# MainBoard_V1.net
KiCad netlist of a schematic drawn in EAGLE
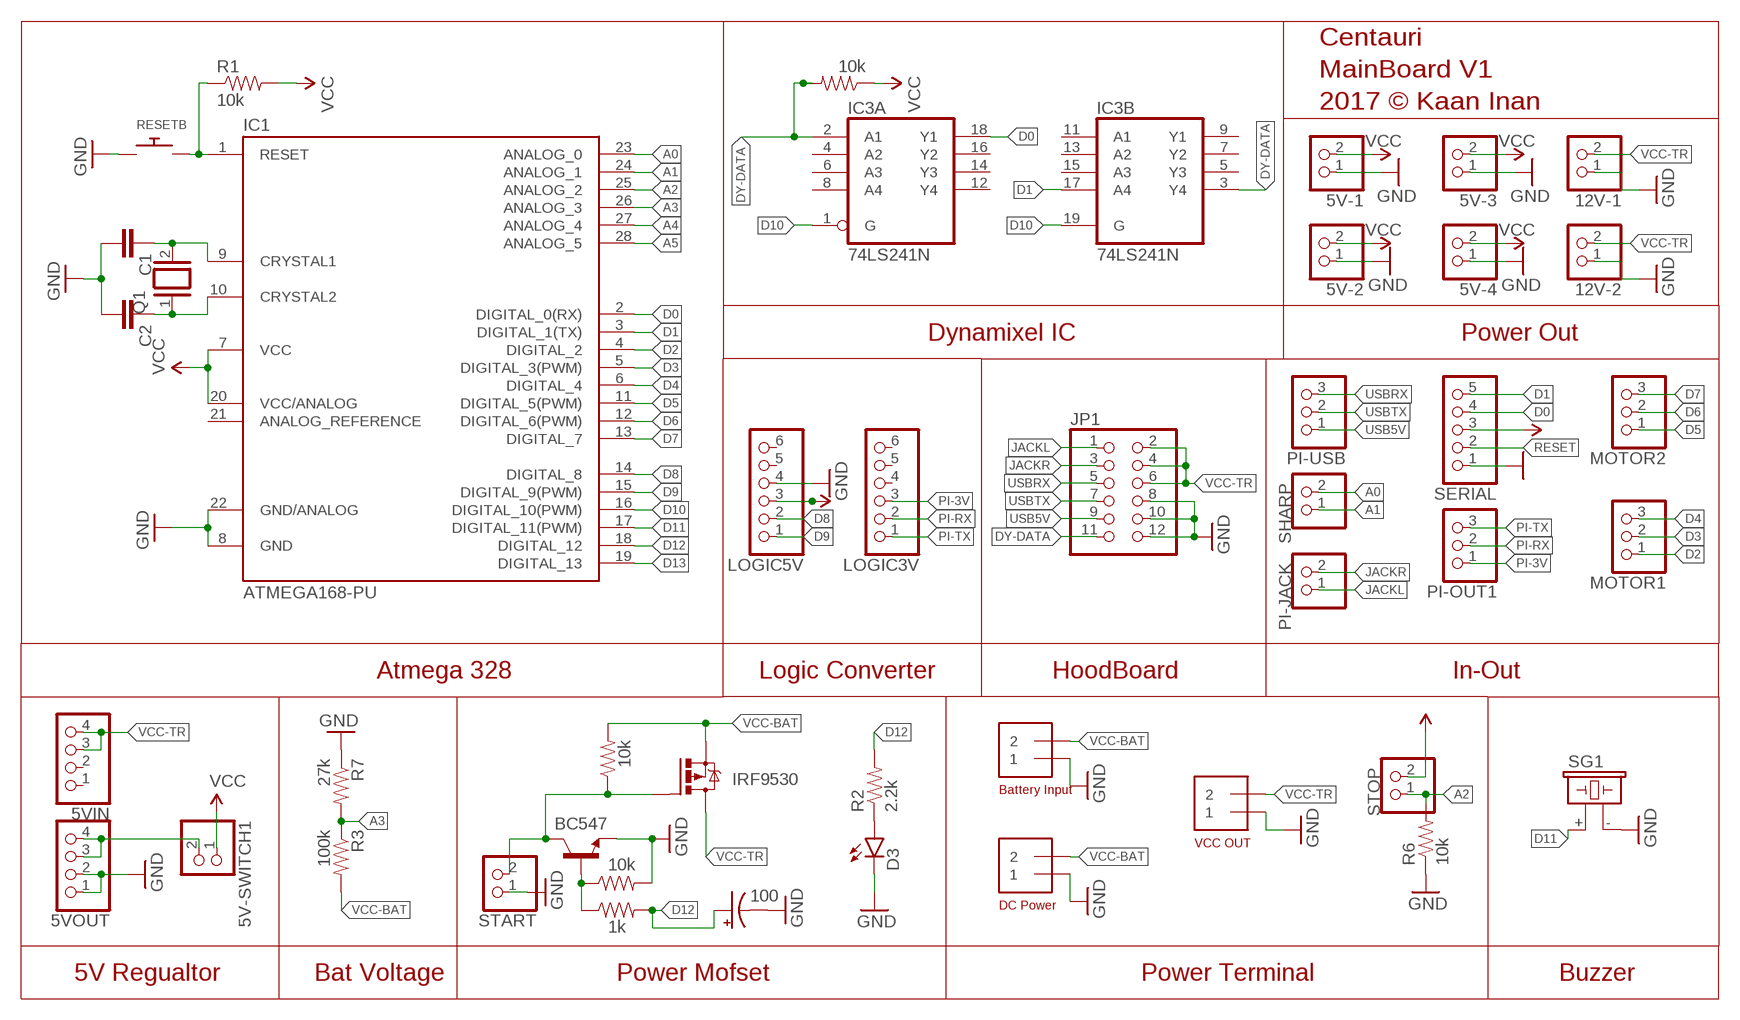
[diagram p0: schematic, sheet 1]

(export (version "E")
  (design (tool "Eeschema 10.0.6"))
  (components
    (comp (ref "5V-1")
      (value "PINHD-1X2/90")
      (footprint "eagle-import:1X02_90")
      (libsource (lib "eagle-import") (part "PINHD-1X2/90"))
    )
    (comp (ref "5V-2")
      (value "PINHD-1X2/90")
      (footprint "eagle-import:1X02_90")
      (libsource (lib "eagle-import") (part "PINHD-1X2/90"))
    )
    (comp (ref "5V-3")
      (value "PINHD-1X2/90")
      (footprint "eagle-import:1X02_90")
      (libsource (lib "eagle-import") (part "PINHD-1X2/90"))
    )
    (comp (ref "5V-4")
      (value "PINHD-1X2/90")
      (footprint "eagle-import:1X02_90")
      (libsource (lib "eagle-import") (part "PINHD-1X2/90"))
    )
    (comp (ref "5V-SWITCH1")
      (value "PINHD-1X2")
      (footprint "eagle-import:1X02")
      (libsource (lib "eagle-import") (part "PINHD-1X2"))
    )
    (comp (ref "5VIN")
      (value "PINHD-1X4")
      (footprint "eagle-import:1X04")
      (libsource (lib "eagle-import") (part "PINHD-1X4"))
    )
    (comp (ref "5VOUT")
      (value "PINHD-1X4")
      (footprint "eagle-import:1X04")
      (libsource (lib "eagle-import") (part "PINHD-1X4"))
    )
    (comp (ref "12V-1")
      (value "PINHD-1X2/90")
      (footprint "eagle-import:1X02_90")
      (libsource (lib "eagle-import") (part "PINHD-1X2/90"))
    )
    (comp (ref "12V-2")
      (value "PINHD-1X2/90")
      (footprint "eagle-import:1X02_90")
      (libsource (lib "eagle-import") (part "PINHD-1X2/90"))
    )
    (comp (ref "C1")
      (value "0.1UF-50V-20%(PTH)KIT-EZ")
      (footprint "eagle-import:CAP-PTH-SMALL-KIT")
      (libsource (lib "eagle-import") (part "0.1UF-50V-20%(PTH)KIT-EZ"))
    )
    (comp (ref "C2")
      (value "0.1UF-50V-20%(PTH)KIT-EZ")
      (footprint "eagle-import:CAP-PTH-SMALL-KIT")
      (libsource (lib "eagle-import") (part "0.1UF-50V-20%(PTH)KIT-EZ"))
    )
    (comp (ref "C7")
      (value "100")
      (footprint "eagle-import:CPOL-RADIAL-100UF-25V")
      (libsource (lib "eagle-import") (part "100UF-25V-20%(PTH)"))
    )
    (comp (ref "D3")
      (value "LED3MM")
      (footprint "eagle-import:LED3MM")
      (libsource (lib "eagle-import") (part "LED3MM"))
    )
    (comp (ref "DC1")
      (value "1X2-3.5MM")
      (footprint "eagle-import:1X2-3.5MM")
      (libsource (lib "eagle-import") (part "1X2-3.5MM"))
    )
    (comp (ref "IC1")
      (value "ATMEGA168-PU")
      (footprint "eagle-import:DIL28-3")
      (libsource (lib "eagle-import") (part "ATMEGA168-PU"))
    )
    (comp (ref "IC3")
      (value "74LS241N")
      (footprint "eagle-import:DIL20")
      (libsource (lib "eagle-import") (part "74241NLS"))
    )
    (comp (ref "JP1")
      (value "PINHD-2X6")
      (footprint "eagle-import:2X06")
      (libsource (lib "eagle-import") (part "PINHD-2X6"))
    )
    (comp (ref "LOGIC3V")
      (value "PINHD-1X6")
      (footprint "eagle-import:1X06")
      (libsource (lib "eagle-import") (part "PINHD-1X6"))
    )
    (comp (ref "LOGIC5V")
      (value "PINHD-1X6")
      (footprint "eagle-import:1X06")
      (libsource (lib "eagle-import") (part "PINHD-1X6"))
    )
    (comp (ref "MOTOR1")
      (value "PINHD-1X3")
      (footprint "eagle-import:1X03")
      (libsource (lib "eagle-import") (part "PINHD-1X3"))
    )
    (comp (ref "MOTOR2")
      (value "PINHD-1X3")
      (footprint "eagle-import:1X03")
      (libsource (lib "eagle-import") (part "PINHD-1X3"))
    )
    (comp (ref "PI-JACK")
      (value "PINHD-1X2")
      (footprint "eagle-import:1X02")
      (libsource (lib "eagle-import") (part "PINHD-1X2"))
    )
    (comp (ref "PI-OUT1")
      (value "PINHD-1X3")
      (footprint "eagle-import:1X03")
      (libsource (lib "eagle-import") (part "PINHD-1X3"))
    )
    (comp (ref "PI-USB")
      (value "PINHD-1X3")
      (footprint "eagle-import:1X03")
      (libsource (lib "eagle-import") (part "PINHD-1X3"))
    )
    (comp (ref "PIL1")
      (value "1X2-3.5MM")
      (footprint "eagle-import:1X2-3.5MM")
      (libsource (lib "eagle-import") (part "1X2-3.5MM"))
    )
    (comp (ref "Q1")
      (value "XTAL/S")
      (footprint "eagle-import:QS")
      (libsource (lib "eagle-import") (part "XTAL/S"))
    )
    (comp (ref "Q2")
      (value "IRF9530")
      (footprint "eagle-import:TO220BV")
      (libsource (lib "eagle-import") (part "IRF9530"))
    )
    (comp (ref "Q6")
      (value "BC547")
      (footprint "eagle-import:TO-92")
      (libsource (lib "eagle-import") (part "TRANSISTOR_NPN2N3904"))
    )
    (comp (ref "R1")
      (value "10k")
      (footprint "eagle-import:AXIAL-0.3")
      (libsource (lib "eagle-import") (part "RESISTORAXIAL-0.3"))
    )
    (comp (ref "R2")
      (value "2.2k")
      (footprint "eagle-import:AXIAL-0.3")
      (libsource (lib "eagle-import") (part "RESISTORAXIAL-0.3"))
    )
    (comp (ref "R3")
      (value "100k")
      (footprint "eagle-import:AXIAL-0.3")
      (libsource (lib "eagle-import") (part "RESISTORAXIAL-0.3"))
    )
    (comp (ref "R6")
      (value "10k")
      (footprint "eagle-import:AXIAL-0.3")
      (libsource (lib "eagle-import") (part "RESISTORAXIAL-0.3"))
    )
    (comp (ref "R7")
      (value "27k")
      (footprint "eagle-import:AXIAL-0.3")
      (libsource (lib "eagle-import") (part "RESISTORAXIAL-0.3"))
    )
    (comp (ref "R8")
      (value "10k")
      (footprint "eagle-import:AXIAL-0.3")
      (libsource (lib "eagle-import") (part "RESISTORAXIAL-0.3"))
    )
    (comp (ref "R17")
      (value "10k")
      (footprint "eagle-import:AXIAL-0.3")
      (libsource (lib "eagle-import") (part "RESISTORAXIAL-0.3"))
    )
    (comp (ref "R19")
      (value "10k")
      (footprint "eagle-import:AXIAL-0.3")
      (libsource (lib "eagle-import") (part "RESISTORAXIAL-0.3"))
    )
    (comp (ref "R20")
      (value "1k")
      (footprint "eagle-import:AXIAL-0.3")
      (libsource (lib "eagle-import") (part "RESISTORAXIAL-0.3"))
    )
    (comp (ref "RESETB")
      (value "SWITCH_PUSHBUTTONEVQ-PE")
      (footprint "eagle-import:TACT_PANA-EVQ")
      (libsource (lib "eagle-import") (part "SWITCH_PUSHBUTTONEVQ-PE"))
    )
    (comp (ref "SERIAL")
      (value "PINHD-1X5")
      (footprint "eagle-import:1X05")
      (libsource (lib "eagle-import") (part "PINHD-1X5"))
    )
    (comp (ref "SG1")
      (value "F/CM12P")
      (footprint "eagle-import:F_CM12P")
      (libsource (lib "eagle-import") (part "F/CM12P"))
    )
    (comp (ref "SHARP")
      (value "PINHD-1X2")
      (footprint "eagle-import:1X02")
      (libsource (lib "eagle-import") (part "PINHD-1X2"))
    )
    (comp (ref "START")
      (value "PINHD-1X2")
      (footprint "eagle-import:1X02")
      (libsource (lib "eagle-import") (part "PINHD-1X2"))
    )
    (comp (ref "STOP")
      (value "PINHD-1X2")
      (footprint "eagle-import:1X02")
      (libsource (lib "eagle-import") (part "PINHD-1X2"))
    )
    (comp (ref "VCC1")
      (value "1X2-3.5MM")
      (footprint "eagle-import:1X2-3.5MM")
      (libsource (lib "eagle-import") (part "1X2-3.5MM"))
    )
  )
  (nets
    (net (code "1") (name "A0") (class "Default")
      (node (ref "IC1") (pin "23") (pinfunction "ANALOG_0_23") (pintype "bidirectional"))
      (node (ref "SHARP") (pin "2") (pinfunction "2_2") (pintype "passive"))
    )
    (net (code "2") (name "A1") (class "Default")
      (node (ref "IC1") (pin "24") (pinfunction "ANALOG_1_24") (pintype "bidirectional"))
      (node (ref "SHARP") (pin "1") (pinfunction "1_1") (pintype "passive"))
    )
    (net (code "3") (name "A2") (class "Default")
      (node (ref "IC1") (pin "25") (pinfunction "ANALOG_2_25") (pintype "bidirectional"))
      (node (ref "R6") (pin "P$2") (pinfunction "2_P$2") (pintype "passive"))
      (node (ref "STOP") (pin "1") (pinfunction "1_1") (pintype "passive"))
    )
    (net (code "4") (name "A3") (class "Default")
      (node (ref "IC1") (pin "26") (pinfunction "ANALOG_3_26") (pintype "bidirectional"))
      (node (ref "R3") (pin "P$1") (pinfunction "1_P$1") (pintype "passive"))
      (node (ref "R7") (pin "P$2") (pinfunction "2_P$2") (pintype "passive"))
    )
    (net (code "5") (name "A4") (class "Default")
      (node (ref "IC1") (pin "27") (pinfunction "ANALOG_4_27") (pintype "bidirectional"))
    )
    (net (code "6") (name "A5") (class "Default")
      (node (ref "IC1") (pin "28") (pinfunction "ANALOG_5_28") (pintype "bidirectional"))
    )
    (net (code "7") (name "D0") (class "Default")
      (node (ref "IC1") (pin "2") (pinfunction "DIGITAL_0(RX)_2") (pintype "bidirectional"))
      (node (ref "IC3") (pin "18") (pinfunction "Y1_18") (pintype "tri_state"))
      (node (ref "SERIAL") (pin "4") (pinfunction "4_4") (pintype "passive"))
    )
    (net (code "8") (name "D1") (class "Default")
      (node (ref "IC1") (pin "3") (pinfunction "DIGITAL_1(TX)_3") (pintype "bidirectional"))
      (node (ref "IC3") (pin "17") (pinfunction "A4_17") (pintype "input"))
      (node (ref "SERIAL") (pin "5") (pinfunction "5_5") (pintype "passive"))
    )
    (net (code "9") (name "D2") (class "Default")
      (node (ref "IC1") (pin "4") (pinfunction "DIGITAL_2_4") (pintype "bidirectional"))
      (node (ref "MOTOR1") (pin "1") (pinfunction "1_1") (pintype "passive"))
    )
    (net (code "10") (name "D3") (class "Default")
      (node (ref "IC1") (pin "5") (pinfunction "DIGITAL_3(PWM)_5") (pintype "bidirectional"))
      (node (ref "MOTOR1") (pin "2") (pinfunction "2_2") (pintype "passive"))
    )
    (net (code "11") (name "D4") (class "Default")
      (node (ref "IC1") (pin "6") (pinfunction "DIGITAL_4_6") (pintype "bidirectional"))
      (node (ref "MOTOR1") (pin "3") (pinfunction "3_3") (pintype "passive"))
    )
    (net (code "12") (name "D5") (class "Default")
      (node (ref "IC1") (pin "11") (pinfunction "DIGITAL_5(PWM)_11") (pintype "bidirectional"))
      (node (ref "MOTOR2") (pin "1") (pinfunction "1_1") (pintype "passive"))
    )
    (net (code "13") (name "D6") (class "Default")
      (node (ref "IC1") (pin "12") (pinfunction "DIGITAL_6(PWM)_12") (pintype "bidirectional"))
      (node (ref "MOTOR2") (pin "2") (pinfunction "2_2") (pintype "passive"))
    )
    (net (code "14") (name "D7") (class "Default")
      (node (ref "IC1") (pin "13") (pinfunction "DIGITAL_7_13") (pintype "bidirectional"))
      (node (ref "MOTOR2") (pin "3") (pinfunction "3_3") (pintype "passive"))
    )
    (net (code "15") (name "D8") (class "Default")
      (node (ref "IC1") (pin "14") (pinfunction "DIGITAL_8_14") (pintype "bidirectional"))
      (node (ref "LOGIC5V") (pin "2") (pinfunction "2_2") (pintype "passive"))
    )
    (net (code "16") (name "D9") (class "Default")
      (node (ref "IC1") (pin "15") (pinfunction "DIGITAL_9(PWM)_15") (pintype "bidirectional"))
      (node (ref "LOGIC5V") (pin "1") (pinfunction "1_1") (pintype "passive"))
    )
    (net (code "17") (name "D10") (class "Default")
      (node (ref "IC1") (pin "16") (pinfunction "DIGITAL_10(PWM)_16") (pintype "bidirectional"))
      (node (ref "IC3") (pin "1") (pinfunction "G_1") (pintype "input"))
      (node (ref "IC3") (pin "19") (pinfunction "G_19") (pintype "input"))
    )
    (net (code "18") (name "D11") (class "Default")
      (node (ref "IC1") (pin "17") (pinfunction "DIGITAL_11(PWM)_17") (pintype "bidirectional"))
      (node (ref "SG1") (pin "+") (pinfunction "1_+") (pintype "passive"))
    )
    (net (code "19") (name "D12") (class "Default")
      (node (ref "C7") (pin "1") (pinfunction "+_1") (pintype "passive"))
      (node (ref "IC1") (pin "18") (pinfunction "DIGITAL_12_18") (pintype "bidirectional"))
      (node (ref "R2") (pin "P$2") (pinfunction "2_P$2") (pintype "passive"))
      (node (ref "R20") (pin "P$2") (pinfunction "2_P$2") (pintype "passive"))
    )
    (net (code "20") (name "D13") (class "Default")
      (node (ref "IC1") (pin "19") (pinfunction "DIGITAL_13_19") (pintype "bidirectional"))
    )
    (net (code "21") (name "DY-DATA") (class "Default")
      (node (ref "IC3") (pin "2") (pinfunction "A1_2") (pintype "input"))
      (node (ref "IC3") (pin "3") (pinfunction "Y4_3") (pintype "tri_state"))
      (node (ref "JP1") (pin "11") (pinfunction "11_11") (pintype "passive"))
      (node (ref "R8") (pin "P$2") (pinfunction "2_P$2") (pintype "passive"))
    )
    (net (code "22") (name "GND") (class "Default")
      (node (ref "12V-1") (pin "1") (pinfunction "1_1") (pintype "passive"))
      (node (ref "12V-2") (pin "1") (pinfunction "1_1") (pintype "passive"))
      (node (ref "5V-1") (pin "1") (pinfunction "1_1") (pintype "passive"))
      (node (ref "5V-2") (pin "1") (pinfunction "1_1") (pintype "passive"))
      (node (ref "5V-3") (pin "1") (pinfunction "1_1") (pintype "passive"))
      (node (ref "5V-4") (pin "1") (pinfunction "1_1") (pintype "passive"))
      (node (ref "5VOUT") (pin "1") (pinfunction "1_1") (pintype "passive"))
      (node (ref "5VOUT") (pin "2") (pinfunction "2_2") (pintype "passive"))
      (node (ref "C1") (pin "2") (pinfunction "2_2") (pintype "passive"))
      (node (ref "C2") (pin "2") (pinfunction "2_2") (pintype "passive"))
      (node (ref "C7") (pin "2") (pinfunction "-_2") (pintype "passive"))
      (node (ref "D3") (pin "K") (pinfunction "C_K") (pintype "passive"))
      (node (ref "DC1") (pin "1") (pinfunction "1_1") (pintype "passive"))
      (node (ref "IC1") (pin "22") (pinfunction "GND/ANALOG_22") (pintype "power_in"))
      (node (ref "IC1") (pin "8") (pinfunction "GND_8") (pintype "power_in"))
      (node (ref "JP1") (pin "10") (pinfunction "10_10") (pintype "passive"))
      (node (ref "JP1") (pin "12") (pinfunction "12_12") (pintype "passive"))
      (node (ref "JP1") (pin "8") (pinfunction "8_8") (pintype "passive"))
      (node (ref "LOGIC5V") (pin "4") (pinfunction "4_4") (pintype "passive"))
      (node (ref "PIL1") (pin "1") (pinfunction "1_1") (pintype "passive"))
      (node (ref "Q6") (pin "3") (pinfunction "E_3") (pintype "passive"))
      (node (ref "R19") (pin "P$2") (pinfunction "2_P$2") (pintype "passive"))
      (node (ref "R6") (pin "P$1") (pinfunction "1_P$1") (pintype "passive"))
      (node (ref "R7") (pin "P$1") (pinfunction "1_P$1") (pintype "passive"))
      (node (ref "RESETB") (pin "P$1") (pinfunction "P$1_P$1") (pintype "passive"))
      (node (ref "SERIAL") (pin "1") (pinfunction "1_1") (pintype "passive"))
      (node (ref "SG1") (pin "-") (pinfunction "2_-") (pintype "passive"))
      (node (ref "START") (pin "1") (pinfunction "1_1") (pintype "passive"))
      (node (ref "VCC1") (pin "1") (pinfunction "1_1") (pintype "passive"))
    )
    (net (code "23") (name "JACKL") (class "Default")
      (node (ref "JP1") (pin "1") (pinfunction "1_1") (pintype "passive"))
      (node (ref "PI-JACK") (pin "1") (pinfunction "1_1") (pintype "passive"))
    )
    (net (code "24") (name "JACKR") (class "Default")
      (node (ref "JP1") (pin "3") (pinfunction "3_3") (pintype "passive"))
      (node (ref "PI-JACK") (pin "2") (pinfunction "2_2") (pintype "passive"))
    )
    (net (code "25") (name "Net-(5V-SWITCH1-Pad2)") (class "Default")
      (node (ref "5V-SWITCH1") (pin "2") (pinfunction "2_2") (pintype "passive"))
      (node (ref "5VOUT") (pin "3") (pinfunction "3_3") (pintype "passive"))
      (node (ref "5VOUT") (pin "4") (pinfunction "4_4") (pintype "passive"))
    )
    (net (code "26") (name "Net-(IC1-CRYSTAL1)") (class "Default")
      (node (ref "C1") (pin "1") (pinfunction "1_1") (pintype "passive"))
      (node (ref "IC1") (pin "9") (pinfunction "CRYSTAL1_9") (pintype "bidirectional"))
      (node (ref "Q1") (pin "2") (pinfunction "2_2") (pintype "passive"))
    )
    (net (code "27") (name "Net-(IC1-CRYSTAL2)") (class "Default")
      (node (ref "C2") (pin "1") (pinfunction "1_1") (pintype "passive"))
      (node (ref "IC1") (pin "10") (pinfunction "CRYSTAL2_10") (pintype "bidirectional"))
      (node (ref "Q1") (pin "1") (pinfunction "1_1") (pintype "passive"))
    )
    (net (code "28") (name "Net-(Q6-B)") (class "Default")
      (node (ref "Q6") (pin "2") (pinfunction "B_2") (pintype "passive"))
      (node (ref "R19") (pin "P$1") (pinfunction "1_P$1") (pintype "passive"))
      (node (ref "R20") (pin "P$1") (pinfunction "1_P$1") (pintype "passive"))
    )
    (net (code "29") (name "Net-(Q6-C)") (class "Default")
      (node (ref "Q2") (pin "G") (pinfunction "G_G") (pintype "passive"))
      (node (ref "Q6") (pin "1") (pinfunction "C_1") (pintype "passive"))
      (node (ref "R17") (pin "P$1") (pinfunction "1_P$1") (pintype "passive"))
      (node (ref "START") (pin "2") (pinfunction "2_2") (pintype "passive"))
    )
    (net (code "30") (name "Net-(R2-1)") (class "Default")
      (node (ref "D3") (pin "A") (pinfunction "A_A") (pintype "passive"))
      (node (ref "R2") (pin "P$1") (pinfunction "1_P$1") (pintype "passive"))
    )
    (net (code "31") (name "PI-3V") (class "Default")
      (node (ref "LOGIC3V") (pin "3") (pinfunction "3_3") (pintype "passive"))
      (node (ref "PI-OUT1") (pin "1") (pinfunction "1_1") (pintype "passive"))
    )
    (net (code "32") (name "PI-RX") (class "Default")
      (node (ref "LOGIC3V") (pin "2") (pinfunction "2_2") (pintype "passive"))
      (node (ref "PI-OUT1") (pin "2") (pinfunction "2_2") (pintype "passive"))
    )
    (net (code "33") (name "PI-TX") (class "Default")
      (node (ref "LOGIC3V") (pin "1") (pinfunction "1_1") (pintype "passive"))
      (node (ref "PI-OUT1") (pin "3") (pinfunction "3_3") (pintype "passive"))
    )
    (net (code "34") (name "RESET") (class "Default")
      (node (ref "IC1") (pin "1") (pinfunction "RESET_1") (pintype "bidirectional"))
      (node (ref "R1") (pin "P$1") (pinfunction "1_P$1") (pintype "passive"))
      (node (ref "RESETB") (pin "P$2") (pinfunction "P$2_P$2") (pintype "passive"))
      (node (ref "SERIAL") (pin "2") (pinfunction "2_2") (pintype "passive"))
    )
    (net (code "35") (name "USB5V") (class "Default")
      (node (ref "JP1") (pin "9") (pinfunction "9_9") (pintype "passive"))
      (node (ref "PI-USB") (pin "1") (pinfunction "1_1") (pintype "passive"))
    )
    (net (code "36") (name "USBRX") (class "Default")
      (node (ref "JP1") (pin "5") (pinfunction "5_5") (pintype "passive"))
      (node (ref "PI-USB") (pin "3") (pinfunction "3_3") (pintype "passive"))
    )
    (net (code "37") (name "USBTX") (class "Default")
      (node (ref "JP1") (pin "7") (pinfunction "7_7") (pintype "passive"))
      (node (ref "PI-USB") (pin "2") (pinfunction "2_2") (pintype "passive"))
    )
    (net (code "38") (name "VCC") (class "Default")
      (node (ref "5V-1") (pin "2") (pinfunction "2_2") (pintype "passive"))
      (node (ref "5V-2") (pin "2") (pinfunction "2_2") (pintype "passive"))
      (node (ref "5V-3") (pin "2") (pinfunction "2_2") (pintype "passive"))
      (node (ref "5V-4") (pin "2") (pinfunction "2_2") (pintype "passive"))
      (node (ref "5V-SWITCH1") (pin "1") (pinfunction "1_1") (pintype "passive"))
      (node (ref "IC1") (pin "20") (pinfunction "VCC/ANALOG_20") (pintype "passive"))
      (node (ref "IC1") (pin "7") (pinfunction "VCC_7") (pintype "power_in"))
      (node (ref "LOGIC5V") (pin "3") (pinfunction "3_3") (pintype "passive"))
      (node (ref "R1") (pin "P$2") (pinfunction "2_P$2") (pintype "passive"))
      (node (ref "R8") (pin "P$1") (pinfunction "1_P$1") (pintype "passive"))
      (node (ref "SERIAL") (pin "3") (pinfunction "3_3") (pintype "passive"))
      (node (ref "STOP") (pin "2") (pinfunction "2_2") (pintype "passive"))
    )
    (net (code "39") (name "VCC-BAT") (class "Default")
      (node (ref "DC1") (pin "2") (pinfunction "2_2") (pintype "passive"))
      (node (ref "PIL1") (pin "2") (pinfunction "2_2") (pintype "passive"))
      (node (ref "Q2") (pin "S") (pinfunction "S_S") (pintype "passive"))
      (node (ref "R17") (pin "P$2") (pinfunction "2_P$2") (pintype "passive"))
      (node (ref "R3") (pin "P$2") (pinfunction "2_P$2") (pintype "passive"))
    )
    (net (code "40") (name "VCC-TR") (class "Default")
      (node (ref "12V-1") (pin "2") (pinfunction "2_2") (pintype "passive"))
      (node (ref "12V-2") (pin "2") (pinfunction "2_2") (pintype "passive"))
      (node (ref "5VIN") (pin "3") (pinfunction "3_3") (pintype "passive"))
      (node (ref "5VIN") (pin "4") (pinfunction "4_4") (pintype "passive"))
      (node (ref "JP1") (pin "2") (pinfunction "2_2") (pintype "passive"))
      (node (ref "JP1") (pin "4") (pinfunction "4_4") (pintype "passive"))
      (node (ref "JP1") (pin "6") (pinfunction "6_6") (pintype "passive"))
      (node (ref "Q2") (pin "D") (pinfunction "D_D") (pintype "passive"))
      (node (ref "VCC1") (pin "2") (pinfunction "2_2") (pintype "passive"))
    )
    (net (code "41") (name "unconnected-(5VIN-Pad1)") (class "Default")
      (node (ref "5VIN") (pin "1") (pinfunction "1_1") (pintype "passive"))
    )
    (net (code "42") (name "unconnected-(5VIN-Pad2)") (class "Default")
      (node (ref "5VIN") (pin "2") (pinfunction "2_2") (pintype "passive"))
    )
    (net (code "43") (name "unconnected-(IC1-ANALOG_REFERENCE-Pad21)") (class "Default")
      (node (ref "IC1") (pin "21") (pinfunction "ANALOG_REFERENCE_21") (pintype "passive"))
    )
    (net (code "44") (name "unconnected-(IC3A-A2-Pad4)") (class "Default")
      (node (ref "IC3") (pin "4") (pinfunction "A2_4") (pintype "input"))
    )
    (net (code "45") (name "unconnected-(IC3A-A3-Pad6)") (class "Default")
      (node (ref "IC3") (pin "6") (pinfunction "A3_6") (pintype "input"))
    )
    (net (code "46") (name "unconnected-(IC3A-A4-Pad8)") (class "Default")
      (node (ref "IC3") (pin "8") (pinfunction "A4_8") (pintype "input"))
    )
    (net (code "47") (name "unconnected-(IC3A-Y2-Pad16)") (class "Default")
      (node (ref "IC3") (pin "16") (pinfunction "Y2_16") (pintype "tri_state"))
    )
    (net (code "48") (name "unconnected-(IC3A-Y3-Pad14)") (class "Default")
      (node (ref "IC3") (pin "14") (pinfunction "Y3_14") (pintype "tri_state"))
    )
    (net (code "49") (name "unconnected-(IC3A-Y4-Pad12)") (class "Default")
      (node (ref "IC3") (pin "12") (pinfunction "Y4_12") (pintype "tri_state"))
    )
    (net (code "50") (name "unconnected-(IC3B-A1-Pad11)") (class "Default")
      (node (ref "IC3") (pin "11") (pinfunction "A1_11") (pintype "input"))
    )
    (net (code "51") (name "unconnected-(IC3B-A2-Pad13)") (class "Default")
      (node (ref "IC3") (pin "13") (pinfunction "A2_13") (pintype "input"))
    )
    (net (code "52") (name "unconnected-(IC3B-A3-Pad15)") (class "Default")
      (node (ref "IC3") (pin "15") (pinfunction "A3_15") (pintype "input"))
    )
    (net (code "53") (name "unconnected-(IC3B-Y1-Pad9)") (class "Default")
      (node (ref "IC3") (pin "9") (pinfunction "Y1_9") (pintype "tri_state"))
    )
    (net (code "54") (name "unconnected-(IC3B-Y2-Pad7)") (class "Default")
      (node (ref "IC3") (pin "7") (pinfunction "Y2_7") (pintype "tri_state"))
    )
    (net (code "55") (name "unconnected-(IC3B-Y3-Pad5)") (class "Default")
      (node (ref "IC3") (pin "5") (pinfunction "Y3_5") (pintype "tri_state"))
    )
    (net (code "56") (name "unconnected-(LOGIC3V-Pad4)") (class "Default")
      (node (ref "LOGIC3V") (pin "4") (pinfunction "4_4") (pintype "passive"))
    )
    (net (code "57") (name "unconnected-(LOGIC3V-Pad5)") (class "Default")
      (node (ref "LOGIC3V") (pin "5") (pinfunction "5_5") (pintype "passive"))
    )
    (net (code "58") (name "unconnected-(LOGIC3V-Pad6)") (class "Default")
      (node (ref "LOGIC3V") (pin "6") (pinfunction "6_6") (pintype "passive"))
    )
    (net (code "59") (name "unconnected-(LOGIC5V-Pad5)") (class "Default")
      (node (ref "LOGIC5V") (pin "5") (pinfunction "5_5") (pintype "passive"))
    )
    (net (code "60") (name "unconnected-(LOGIC5V-Pad6)") (class "Default")
      (node (ref "LOGIC5V") (pin "6") (pinfunction "6_6") (pintype "passive"))
    )
  )
)
